# robotic_arm_arduino_uno_shield_ece196.net
KiCad netlist of a schematic drawn in EAGLE
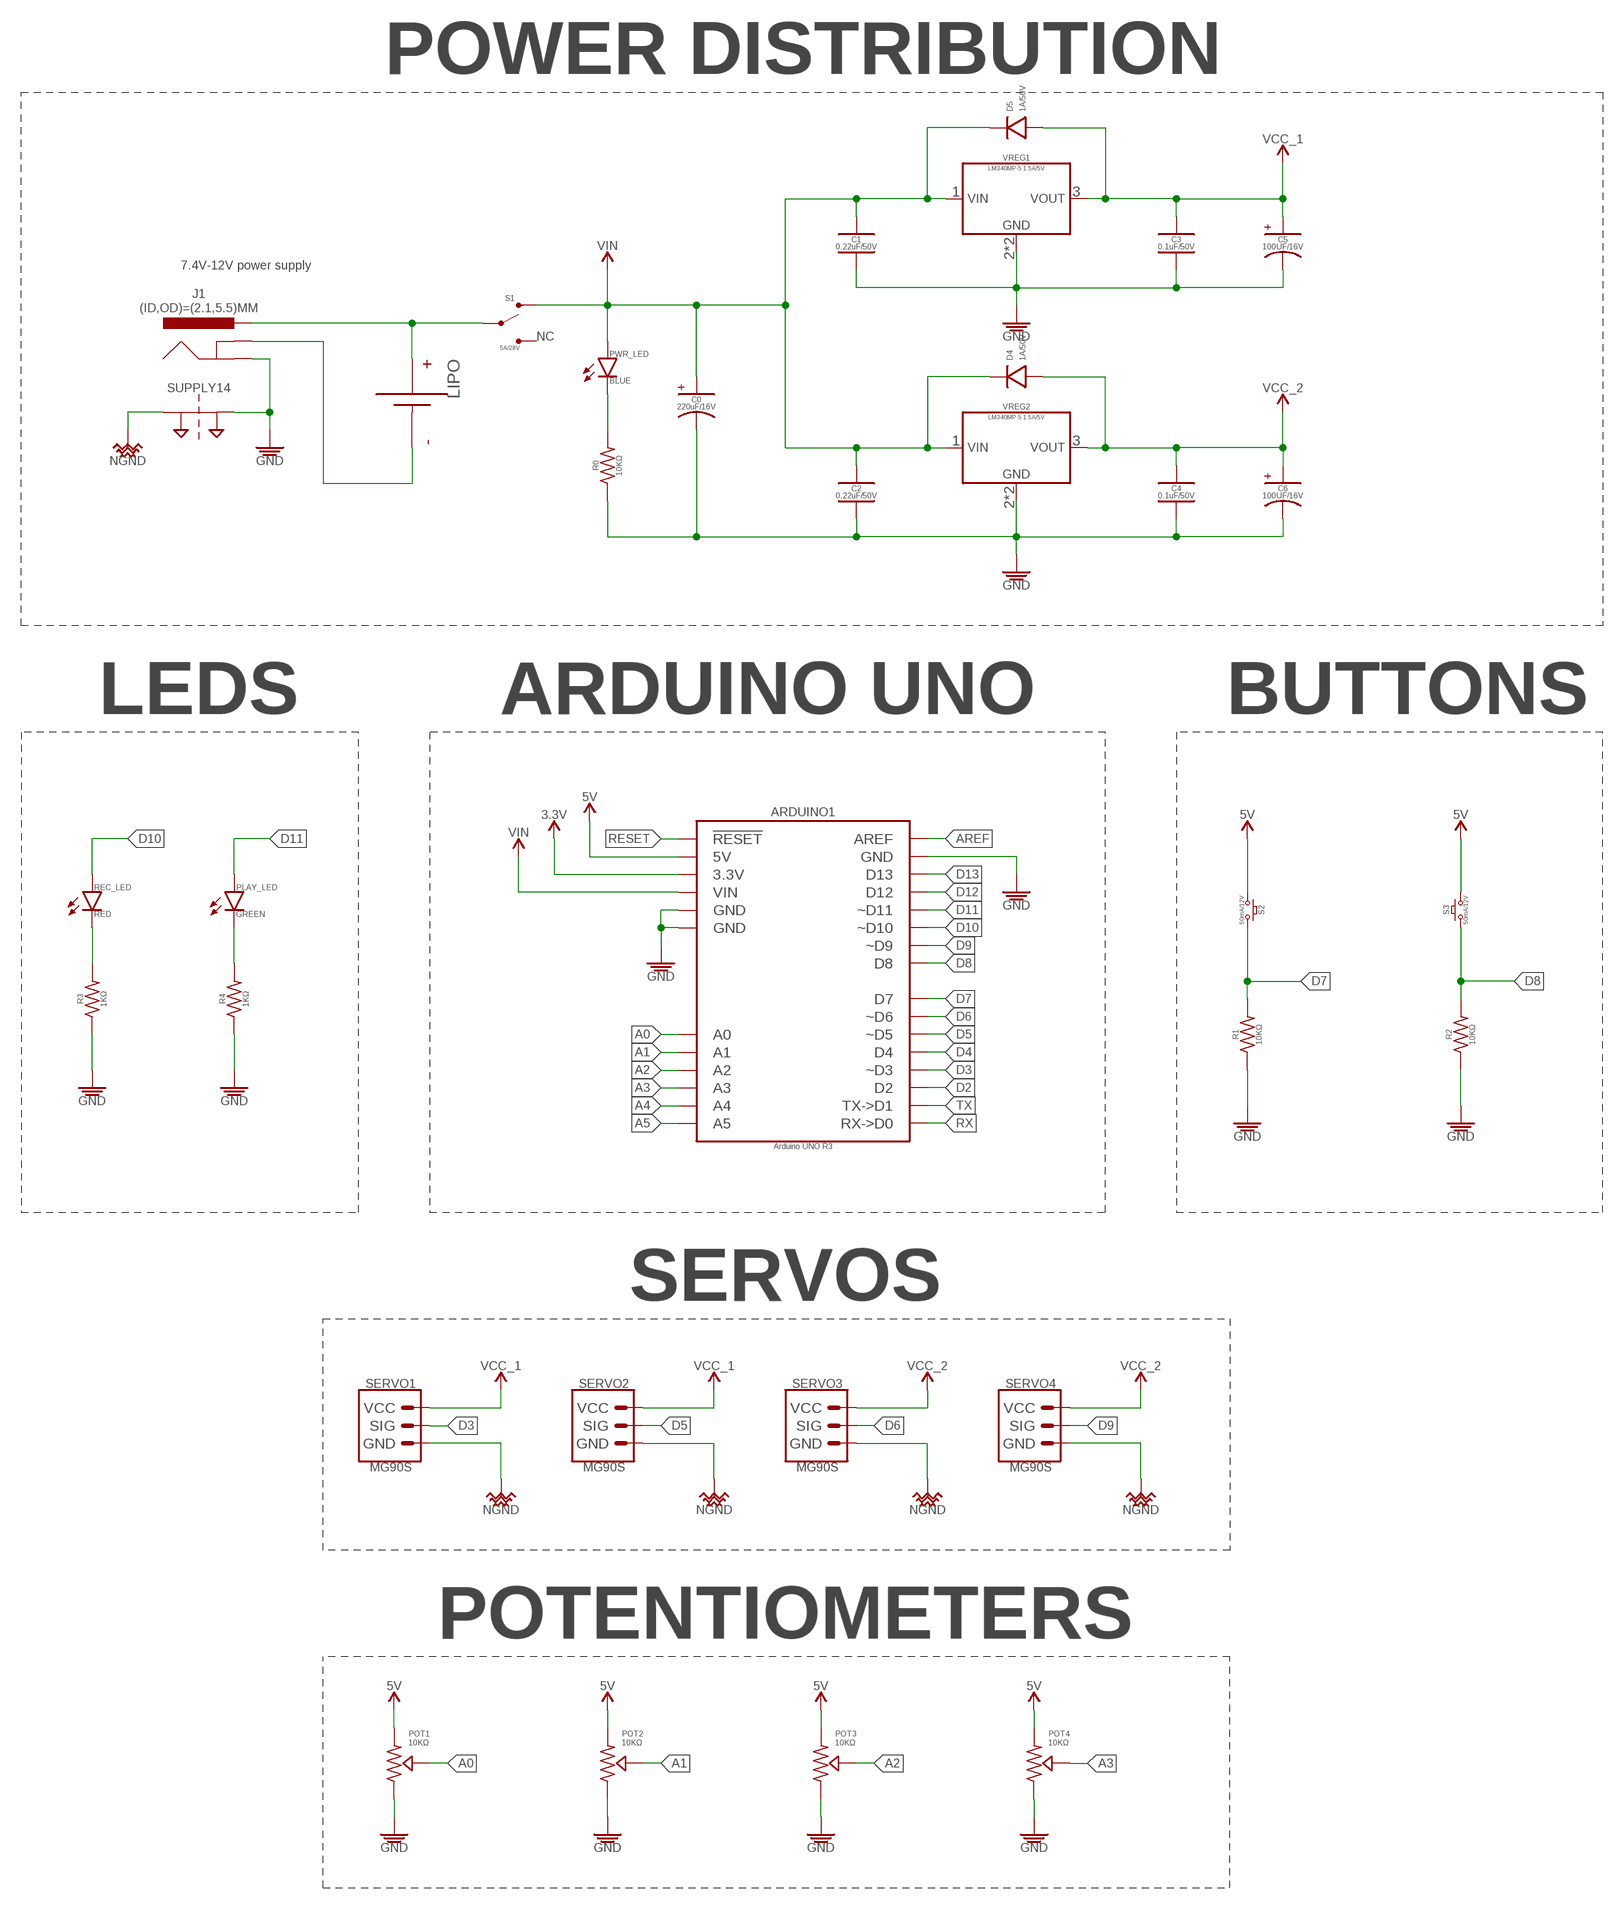
[diagram p0: schematic, sheet 1]

(export (version "E")
  (design (tool "Eeschema 10.0.6"))
  (components
    (comp (ref "ARDUINO1")
      (value "Arduino UNO R3")
      (footprint "eagle-import:ARDUINO_UNO_R3_NO-HOLES_NO-AVR-ISP_NO-I2C_NO-NC_NO-IOREF")
      (fields (field (name "MFR") "Arduino") (field (name "MPN") "A000066"))
      (libsource (lib "eagle-import") (part "ARDUINO_UNO_R3_NO-HOLES_NO-AVR-ISP_NO-I2C_NO-NC_NO-IOREF"))
    )
    (comp (ref "C0")
      (value "220uF/16V")
      (footprint "eagle-import:_AE_SMD_L6.6-W6.6")
      (fields
        (field (name "MFR") "Panasonic Electronic Components")
        (field (name "MPN") "EEE-FT1C221AP")
        (field (name "CREATOR") "MrSwirlyEyes")
      )
      (libsource (lib "eagle-import") (part "220UF-POLARIZED_SMD_16V-20%"))
    )
    (comp (ref "C1")
      (value "0.22uF/50V")
      (footprint "eagle-import:_CER_SMD-805")
      (fields
        (field (name "MFR") "Murata Electronics North America")
        (field (name "MPN") "GRM21BR71H224KA01L")
        (field (name "CREATOR") "MrSwirlyEyes")
      )
      (libsource (lib "eagle-import") (part "0.22UF_SMD-805_50V-10%"))
    )
    (comp (ref "C2")
      (value "0.22uF/50V")
      (footprint "eagle-import:_CER_SMD-805")
      (fields
        (field (name "MFR") "Murata Electronics North America")
        (field (name "MPN") "GRM21BR71H224KA01L")
        (field (name "CREATOR") "MrSwirlyEyes")
      )
      (libsource (lib "eagle-import") (part "0.22UF_SMD-805_50V-10%"))
    )
    (comp (ref "C3")
      (value "0.1uF/50V")
      (footprint "eagle-import:_CER_SMD-805")
      (fields
        (field (name "MFR") "Murata Electronics North America")
        (field (name "MPN") "GRM21BR71H104KA01L")
        (field (name "CREATOR") "MrSwirlyEyes")
      )
      (libsource (lib "eagle-import") (part "0.1UF_SMD-805_50V-10%"))
    )
    (comp (ref "C4")
      (value "0.1uF/50V")
      (footprint "eagle-import:_CER_SMD-805")
      (fields
        (field (name "MFR") "Murata Electronics North America")
        (field (name "MPN") "GRM21BR71H104KA01L")
        (field (name "CREATOR") "MrSwirlyEyes")
      )
      (libsource (lib "eagle-import") (part "0.1UF_SMD-805_50V-10%"))
    )
    (comp (ref "C5")
      (value "100UF/16V")
      (footprint "eagle-import:_AE_SMD_L6.6-W6.6")
      (fields
        (field (name "MFR") "Panasonic Electronic Components")
        (field (name "MPN") "EEE-FK1C101P")
        (field (name "CREATOR") "MrSwirlyEyes")
      )
      (libsource (lib "eagle-import") (part "100UF-POLARIZED_SMD_16V-20%"))
    )
    (comp (ref "C6")
      (value "100UF/16V")
      (footprint "eagle-import:_AE_SMD_L6.6-W6.6")
      (fields
        (field (name "MFR") "Panasonic Electronic Components")
        (field (name "MPN") "EEE-FK1C101P")
        (field (name "CREATOR") "MrSwirlyEyes")
      )
      (libsource (lib "eagle-import") (part "100UF-POLARIZED_SMD_16V-20%"))
    )
    (comp (ref "D4")
      (value "1A/50V")
      (footprint "eagle-import:SOD123F")
      (fields
        (field (name "MFR") "Comchip Technology")
        (field (name "MPN") "CGRKM4001-HF")
        (field (name "CREATOR") "MrSwirlyEyes")
      )
      (libsource (lib "eagle-import") (part "DIODE_GENERAL-PURPOSE_SMD_GP_1A-50V"))
    )
    (comp (ref "D5")
      (value "1A/50V")
      (footprint "eagle-import:SOD123F")
      (fields
        (field (name "MFR") "Comchip Technology")
        (field (name "MPN") "CGRKM4001-HF")
        (field (name "CREATOR") "MrSwirlyEyes")
      )
      (libsource (lib "eagle-import") (part "DIODE_GENERAL-PURPOSE_SMD_GP_1A-50V"))
    )
    (comp (ref "J1")
      (value "(ID,OD)=(2.1,5.5)MM")
      (footprint "eagle-import:POWER_JACK_PTH_ID2.1MM-OD5.5MM")
      (fields (field (name "MFR") "CUI Inc.") (field (name "MPN") "PJ-059A"))
      (libsource (lib "eagle-import") (part "POWER_JACK-BARREL_ID2.1MM-OD5.5MMPTH"))
    )
    (comp (ref "LIPO")
      (value "7.4V")
      (footprint "eagle-import:DUAL_PTH_PADS")
      (libsource (lib "eagle-import") (part "BATTERY_LIPO_BATTERY"))
    )
    (comp (ref "PLAY_LED")
      (value "GREEN")
      (footprint "eagle-import:LED_SMD-805_")
      (fields
        (field (name "MFR") "Lite-On Inc.")
        (field (name "MPN") "LTST-C170KGKT")
        (field (name "CREATOR") "MrSwirlyEyes")
      )
      (libsource (lib "eagle-import") (part "LED_SMD-0805_DISCRETE_GREEN"))
    )
    (comp (ref "POT1")
      (value "10KΩ")
      (footprint "eagle-import:CONNECTOR_POTENTIOMETER_NO-MARKINGS_FEMALE-HEADER")
      (fields
        (field (name "MFR") "TT Electronics/BI")
        (field (name "MPN") "P160KN2-0QA25B10K")
        (field (name "CREATOR") "MrSwirlyEyes")
      )
      (libsource (lib "eagle-import") (part "POTENTIOMETER_NO-MARKINGS_VERT-FEMALE"))
    )
    (comp (ref "POT2")
      (value "10KΩ")
      (footprint "eagle-import:CONNECTOR_POTENTIOMETER_NO-MARKINGS_FEMALE-HEADER")
      (fields
        (field (name "MFR") "TT Electronics/BI")
        (field (name "MPN") "P160KN2-0QA25B10K")
        (field (name "CREATOR") "MrSwirlyEyes")
      )
      (libsource (lib "eagle-import") (part "POTENTIOMETER_NO-MARKINGS_VERT-FEMALE"))
    )
    (comp (ref "POT3")
      (value "10KΩ")
      (footprint "eagle-import:CONNECTOR_POTENTIOMETER_NO-MARKINGS_FEMALE-HEADER")
      (fields
        (field (name "MFR") "TT Electronics/BI")
        (field (name "MPN") "P160KN2-0QA25B10K")
        (field (name "CREATOR") "MrSwirlyEyes")
      )
      (libsource (lib "eagle-import") (part "POTENTIOMETER_NO-MARKINGS_VERT-FEMALE"))
    )
    (comp (ref "POT4")
      (value "10KΩ")
      (footprint "eagle-import:CONNECTOR_POTENTIOMETER_NO-MARKINGS_FEMALE-HEADER")
      (fields
        (field (name "MFR") "TT Electronics/BI")
        (field (name "MPN") "P160KN2-0QA25B10K")
        (field (name "CREATOR") "MrSwirlyEyes")
      )
      (libsource (lib "eagle-import") (part "POTENTIOMETER_NO-MARKINGS_VERT-FEMALE"))
    )
    (comp (ref "PWR_LED")
      (value "BLUE")
      (footprint "eagle-import:LED_SMD-805_")
      (fields
        (field (name "MFR") "Lite-On Inc.")
        (field (name "MPN") "LTST-C170TBKT")
        (field (name "CREATOR") "MrSwirlyEyes")
      )
      (libsource (lib "eagle-import") (part "LED_SMD-0805_DISCRETE_BLUE"))
    )
    (comp (ref "R0")
      (value "10KΩ")
      (footprint "eagle-import:RESISTOR_SMD-805")
      (fields
        (field (name "MFR") "Yageo")
        (field (name "MPN") "RC0805JR-0710KL")
        (field (name "CREATOR") "Kenmei")
      )
      (libsource (lib "eagle-import") (part "10KΩ_SMD-0805_1/8W-5%"))
    )
    (comp (ref "R1")
      (value "10KΩ")
      (footprint "eagle-import:RESISTOR_SMD-805")
      (fields
        (field (name "MFR") "Yageo")
        (field (name "MPN") "RC0805JR-0710KL")
        (field (name "CREATOR") "Kenmei")
      )
      (libsource (lib "eagle-import") (part "10KΩ_SMD-0805_1/8W-5%"))
    )
    (comp (ref "R2")
      (value "10KΩ")
      (footprint "eagle-import:RESISTOR_SMD-805")
      (fields
        (field (name "MFR") "Yageo")
        (field (name "MPN") "RC0805JR-0710KL")
        (field (name "CREATOR") "Kenmei")
      )
      (libsource (lib "eagle-import") (part "10KΩ_SMD-0805_1/8W-5%"))
    )
    (comp (ref "R3")
      (value "1KΩ")
      (footprint "eagle-import:RESISTOR_SMD-805")
      (fields
        (field (name "MFR") "Yageo")
        (field (name "MPN") "RC0805JR-071KL ")
        (field (name "CREATOR") "Kenmei")
      )
      (libsource (lib "eagle-import") (part "1KΩ_SMD-0805_1/8W-5%"))
    )
    (comp (ref "R4")
      (value "1KΩ")
      (footprint "eagle-import:RESISTOR_SMD-805")
      (fields
        (field (name "MFR") "Yageo")
        (field (name "MPN") "RC0805JR-071KL ")
        (field (name "CREATOR") "Kenmei")
      )
      (libsource (lib "eagle-import") (part "1KΩ_SMD-0805_1/8W-5%"))
    )
    (comp (ref "REC_LED")
      (value "RED")
      (footprint "eagle-import:LED_SMD-805_")
      (fields
        (field (name "MFR") "Lite-On Inc.")
        (field (name "MPN") "LTST-C170KRKT")
        (field (name "CREATOR") "MrSwirlyEyes")
      )
      (libsource (lib "eagle-import") (part "LED_SMD-0805_DISCRETE_RED"))
    )
    (comp (ref "S1")
      (value "5A/28V")
      (footprint "eagle-import:SW_TOGGLE_SPDT_5A-28V_13L-7W")
      (fields
        (field (name "MFR") "E-Switch")
        (field (name "MPN") "100SP1T1B4M2QE")
        (field (name "CREATOR") "MrSwirlyEyes")
      )
      (libsource (lib "eagle-import") (part "SWITCH_SPDT_VERT_PTH_5A-28V_13L-7W"))
    )
    (comp (ref "S2")
      (value "50mA/12V")
      (footprint "eagle-import:BTN_MOMENTARY_SPST-NO_PTH_L12-W12")
      (fields
        (field (name "MFR") "SparkFun Electronics")
        (field (name "MPN") "COM-10302")
        (field (name "CREATOR") "MrSwirlyEyes")
      )
      (libsource (lib "eagle-import") (part "SWITCH_MOMENTARYSPST-PTH-L12-W12-H7.2"))
    )
    (comp (ref "S3")
      (value "50mA/12V")
      (footprint "eagle-import:BTN_MOMENTARY_SPST-NO_PTH_L12-W12")
      (fields
        (field (name "MFR") "SparkFun Electronics")
        (field (name "MPN") "COM-10302")
        (field (name "CREATOR") "MrSwirlyEyes")
      )
      (libsource (lib "eagle-import") (part "SWITCH_MOMENTARYSPST-PTH-L12-W12-H7.2"))
    )
    (comp (ref "SERVO1")
      (value "MG90S")
      (footprint "eagle-import:CONNECTOR_SERVO")
      (fields (field (name "MFR") "TowerPro") (field (name "CREATOR") "MrSwirlyEyes"))
      (libsource (lib "eagle-import") (part "SERVOMG90S"))
    )
    (comp (ref "SERVO2")
      (value "MG90S")
      (footprint "eagle-import:CONNECTOR_SERVO")
      (fields (field (name "MFR") "TowerPro") (field (name "CREATOR") "MrSwirlyEyes"))
      (libsource (lib "eagle-import") (part "SERVOMG90S"))
    )
    (comp (ref "SERVO3")
      (value "MG90S")
      (footprint "eagle-import:CONNECTOR_SERVO")
      (fields (field (name "MFR") "TowerPro") (field (name "CREATOR") "MrSwirlyEyes"))
      (libsource (lib "eagle-import") (part "SERVOMG90S"))
    )
    (comp (ref "SERVO4")
      (value "MG90S")
      (footprint "eagle-import:CONNECTOR_SERVO")
      (fields (field (name "MFR") "TowerPro") (field (name "CREATOR") "MrSwirlyEyes"))
      (libsource (lib "eagle-import") (part "SERVOMG90S"))
    )
    (comp (ref "SUPPLY14")
      (value "2PT_GND_TIE")
      (footprint "eagle-import:2PT_GND_TIE")
      (libsource (lib "eagle-import") (part "2PT_GND_TIE"))
    )
    (comp (ref "VREG1")
      (value "LM340MP-5 1.5A/5V")
      (footprint "eagle-import:SOT223-4")
      (fields
        (field (name "MFR") "Texas Instruments")
        (field (name "MPN") "LM340MP-5.0/NOPB")
        (field (name "CREATOR") "MrSwirlyEyes")
      )
      (libsource (lib "eagle-import") (part "VREG_LINEAR_FIXED_LM340MP-5_1.5A-5V"))
    )
    (comp (ref "VREG2")
      (value "LM340MP-5 1.5A/5V")
      (footprint "eagle-import:SOT223-4")
      (fields
        (field (name "MFR") "Texas Instruments")
        (field (name "MPN") "LM340MP-5.0/NOPB")
        (field (name "CREATOR") "MrSwirlyEyes")
      )
      (libsource (lib "eagle-import") (part "VREG_LINEAR_FIXED_LM340MP-5_1.5A-5V"))
    )
  )
  (nets
    (net (code "1") (name "3.3V") (class "Default")
      (node (ref "ARDUINO1") (pin "3.3V") (pinfunction "3.3V_3.3V") (pintype "bidirectional"))
    )
    (net (code "2") (name "5V") (class "Default")
      (node (ref "ARDUINO1") (pin "5V") (pinfunction "5V_5V") (pintype "bidirectional"))
      (node (ref "POT1") (pin "CCW") (pinfunction "CCW_CCW") (pintype "passive"))
      (node (ref "POT2") (pin "CCW") (pinfunction "CCW_CCW") (pintype "passive"))
      (node (ref "POT3") (pin "CCW") (pinfunction "CCW_CCW") (pintype "passive"))
      (node (ref "POT4") (pin "CCW") (pinfunction "CCW_CCW") (pintype "passive"))
      (node (ref "S2") (pin "1") (pinfunction "1_1") (pintype "passive"))
      (node (ref "S3") (pin "3") (pinfunction "2_3") (pintype "passive"))
    )
    (net (code "3") (name "A0") (class "Default")
      (node (ref "ARDUINO1") (pin "A0") (pinfunction "A0_A0") (pintype "bidirectional"))
      (node (ref "POT1") (pin "S") (pinfunction "S_S") (pintype "passive"))
    )
    (net (code "4") (name "A1") (class "Default")
      (node (ref "ARDUINO1") (pin "A1") (pinfunction "A1_A1") (pintype "bidirectional"))
      (node (ref "POT2") (pin "S") (pinfunction "S_S") (pintype "passive"))
    )
    (net (code "5") (name "A2") (class "Default")
      (node (ref "ARDUINO1") (pin "A2") (pinfunction "A2_A2") (pintype "bidirectional"))
      (node (ref "POT3") (pin "S") (pinfunction "S_S") (pintype "passive"))
    )
    (net (code "6") (name "A3") (class "Default")
      (node (ref "ARDUINO1") (pin "A3") (pinfunction "A3_A3") (pintype "bidirectional"))
      (node (ref "POT4") (pin "S") (pinfunction "S_S") (pintype "passive"))
    )
    (net (code "7") (name "A4") (class "Default")
      (node (ref "ARDUINO1") (pin "A4") (pinfunction "A4_A4") (pintype "bidirectional"))
    )
    (net (code "8") (name "A5") (class "Default")
      (node (ref "ARDUINO1") (pin "A5") (pinfunction "A5_A5") (pintype "bidirectional"))
    )
    (net (code "9") (name "AREF") (class "Default")
      (node (ref "ARDUINO1") (pin "AREF") (pinfunction "AREF_AREF") (pintype "bidirectional"))
    )
    (net (code "10") (name "D2") (class "Default")
      (node (ref "ARDUINO1") (pin "D2") (pinfunction "D2_D2") (pintype "bidirectional"))
    )
    (net (code "11") (name "D3") (class "Default")
      (node (ref "ARDUINO1") (pin "D3") (pinfunction "~{D3}_D3") (pintype "bidirectional"))
      (node (ref "SERVO1") (pin "1") (pinfunction "SIG_1") (pintype "passive"))
    )
    (net (code "12") (name "D4") (class "Default")
      (node (ref "ARDUINO1") (pin "D4") (pinfunction "D4_D4") (pintype "bidirectional"))
    )
    (net (code "13") (name "D5") (class "Default")
      (node (ref "ARDUINO1") (pin "D5") (pinfunction "~{D5}_D5") (pintype "bidirectional"))
      (node (ref "SERVO2") (pin "1") (pinfunction "SIG_1") (pintype "passive"))
    )
    (net (code "14") (name "D6") (class "Default")
      (node (ref "ARDUINO1") (pin "D6") (pinfunction "~{D6}_D6") (pintype "bidirectional"))
      (node (ref "SERVO3") (pin "1") (pinfunction "SIG_1") (pintype "passive"))
    )
    (net (code "15") (name "D7") (class "Default")
      (node (ref "ARDUINO1") (pin "D7") (pinfunction "D7_D7") (pintype "bidirectional"))
      (node (ref "R1") (pin "2") (pinfunction "2_2") (pintype "passive"))
      (node (ref "S2") (pin "3") (pinfunction "2_3") (pintype "passive"))
    )
    (net (code "16") (name "D8") (class "Default")
      (node (ref "ARDUINO1") (pin "D8") (pinfunction "D8_D8") (pintype "bidirectional"))
      (node (ref "R2") (pin "2") (pinfunction "2_2") (pintype "passive"))
      (node (ref "S3") (pin "1") (pinfunction "1_1") (pintype "passive"))
    )
    (net (code "17") (name "D9") (class "Default")
      (node (ref "ARDUINO1") (pin "D9") (pinfunction "~{D9}_D9") (pintype "bidirectional"))
      (node (ref "SERVO4") (pin "1") (pinfunction "SIG_1") (pintype "passive"))
    )
    (net (code "18") (name "D10") (class "Default")
      (node (ref "ARDUINO1") (pin "D10") (pinfunction "~{D10}_D10") (pintype "bidirectional"))
      (node (ref "REC_LED") (pin "A") (pinfunction "A_A") (pintype "passive"))
    )
    (net (code "19") (name "D11") (class "Default")
      (node (ref "ARDUINO1") (pin "D11") (pinfunction "~{D11}_D11") (pintype "bidirectional"))
      (node (ref "PLAY_LED") (pin "A") (pinfunction "A_A") (pintype "passive"))
    )
    (net (code "20") (name "D12") (class "Default")
      (node (ref "ARDUINO1") (pin "D12") (pinfunction "D12_D12") (pintype "bidirectional"))
    )
    (net (code "21") (name "D13") (class "Default")
      (node (ref "ARDUINO1") (pin "D13") (pinfunction "D13_D13") (pintype "bidirectional"))
    )
    (net (code "22") (name "GND") (class "Default")
      (node (ref "ARDUINO1") (pin "GND@1") (pinfunction "GND_GND@1") (pintype "bidirectional"))
      (node (ref "ARDUINO1") (pin "GND@2") (pinfunction "GND_GND@2") (pintype "bidirectional"))
      (node (ref "ARDUINO1") (pin "GND@3") (pinfunction "GND_GND@3") (pintype "bidirectional"))
      (node (ref "C0") (pin "K") (pinfunction "K_K") (pintype "passive"))
      (node (ref "C1") (pin "2") (pinfunction "2_2") (pintype "passive"))
      (node (ref "C2") (pin "2") (pinfunction "2_2") (pintype "passive"))
      (node (ref "C3") (pin "2") (pinfunction "2_2") (pintype "passive"))
      (node (ref "C4") (pin "2") (pinfunction "2_2") (pintype "passive"))
      (node (ref "C5") (pin "K") (pinfunction "K_K") (pintype "passive"))
      (node (ref "C6") (pin "K") (pinfunction "K_K") (pintype "passive"))
      (node (ref "J1") (pin "GND@1") (pinfunction "GND_GND@1") (pintype "bidirectional"))
      (node (ref "POT1") (pin "CW") (pinfunction "CW_CW") (pintype "passive"))
      (node (ref "POT2") (pin "CW") (pinfunction "CW_CW") (pintype "passive"))
      (node (ref "POT3") (pin "CW") (pinfunction "CW_CW") (pintype "passive"))
      (node (ref "POT4") (pin "CW") (pinfunction "CW_CW") (pintype "passive"))
      (node (ref "R0") (pin "1") (pinfunction "1_1") (pintype "passive"))
      (node (ref "R1") (pin "1") (pinfunction "1_1") (pintype "passive"))
      (node (ref "R2") (pin "1") (pinfunction "1_1") (pintype "passive"))
      (node (ref "R3") (pin "1") (pinfunction "1_1") (pintype "passive"))
      (node (ref "R4") (pin "1") (pinfunction "1_1") (pintype "passive"))
      (node (ref "SUPPLY14") (pin "P$2") (pinfunction "P$2_P$2") (pintype "bidirectional"))
      (node (ref "VREG1") (pin "2") (pinfunction "GND_2") (pintype "bidirectional"))
      (node (ref "VREG1") (pin "TAB") (pinfunction "GND_TAB") (pintype "bidirectional"))
      (node (ref "VREG2") (pin "2") (pinfunction "GND_2") (pintype "bidirectional"))
      (node (ref "VREG2") (pin "TAB") (pinfunction "GND_TAB") (pintype "bidirectional"))
    )
    (net (code "23") (name "NGND") (class "Default")
      (node (ref "SERVO1") (pin "3") (pinfunction "GND_3") (pintype "passive"))
      (node (ref "SERVO2") (pin "3") (pinfunction "GND_3") (pintype "passive"))
      (node (ref "SERVO3") (pin "3") (pinfunction "GND_3") (pintype "passive"))
      (node (ref "SERVO4") (pin "3") (pinfunction "GND_3") (pintype "passive"))
      (node (ref "SUPPLY14") (pin "P$1") (pinfunction "P$1_P$1") (pintype "bidirectional"))
    )
    (net (code "24") (name "Net-(LIPO-N)") (class "Default")
      (node (ref "J1") (pin "GND@2") (pinfunction "GND_GND@2") (pintype "bidirectional"))
      (node (ref "LIPO") (pin "-") (pinfunction "N_-") (pintype "bidirectional"))
    )
    (net (code "25") (name "Net-(LIPO-P)") (class "Default")
      (node (ref "J1") (pin "PWR") (pinfunction "PWR_PWR") (pintype "bidirectional"))
      (node (ref "LIPO") (pin "+") (pinfunction "P_+") (pintype "bidirectional"))
      (node (ref "S1") (pin "2") (pinfunction "2_2") (pintype "passive"))
    )
    (net (code "26") (name "Net-(PLAY_LED-PadK)") (class "Default")
      (node (ref "PLAY_LED") (pin "K") (pinfunction "K_K") (pintype "passive"))
      (node (ref "R4") (pin "2") (pinfunction "2_2") (pintype "passive"))
    )
    (net (code "27") (name "Net-(PWR_LED-PadK)") (class "Default")
      (node (ref "PWR_LED") (pin "K") (pinfunction "K_K") (pintype "passive"))
      (node (ref "R0") (pin "2") (pinfunction "2_2") (pintype "passive"))
    )
    (net (code "28") (name "Net-(R3-Pad2)") (class "Default")
      (node (ref "R3") (pin "2") (pinfunction "2_2") (pintype "passive"))
      (node (ref "REC_LED") (pin "K") (pinfunction "K_K") (pintype "passive"))
    )
    (net (code "29") (name "RESET") (class "Default")
      (node (ref "ARDUINO1") (pin "RESET@1") (pinfunction "~{RESET}_RESET@1") (pintype "bidirectional"))
    )
    (net (code "30") (name "RX") (class "Default")
      (node (ref "ARDUINO1") (pin "D0") (pinfunction "RX->D0_D0") (pintype "bidirectional"))
    )
    (net (code "31") (name "TX") (class "Default")
      (node (ref "ARDUINO1") (pin "D1") (pinfunction "TX->D1_D1") (pintype "bidirectional"))
    )
    (net (code "32") (name "VCC_1") (class "Default")
      (node (ref "C3") (pin "1") (pinfunction "1_1") (pintype "passive"))
      (node (ref "C5") (pin "A") (pinfunction "A_A") (pintype "passive"))
      (node (ref "D5") (pin "A") (pinfunction "A_A") (pintype "passive"))
      (node (ref "SERVO1") (pin "2") (pinfunction "VCC_2") (pintype "passive"))
      (node (ref "SERVO2") (pin "2") (pinfunction "VCC_2") (pintype "passive"))
      (node (ref "VREG1") (pin "3") (pinfunction "VO_3") (pintype "bidirectional"))
    )
    (net (code "33") (name "VCC_2") (class "Default")
      (node (ref "C4") (pin "1") (pinfunction "1_1") (pintype "passive"))
      (node (ref "C6") (pin "A") (pinfunction "A_A") (pintype "passive"))
      (node (ref "D4") (pin "A") (pinfunction "A_A") (pintype "passive"))
      (node (ref "SERVO3") (pin "2") (pinfunction "VCC_2") (pintype "passive"))
      (node (ref "SERVO4") (pin "2") (pinfunction "VCC_2") (pintype "passive"))
      (node (ref "VREG2") (pin "3") (pinfunction "VO_3") (pintype "bidirectional"))
    )
    (net (code "34") (name "VIN") (class "Default")
      (node (ref "ARDUINO1") (pin "VIN") (pinfunction "VIN_VIN") (pintype "bidirectional"))
      (node (ref "C0") (pin "A") (pinfunction "A_A") (pintype "passive"))
      (node (ref "C1") (pin "1") (pinfunction "1_1") (pintype "passive"))
      (node (ref "C2") (pin "1") (pinfunction "1_1") (pintype "passive"))
      (node (ref "D4") (pin "K") (pinfunction "K_K") (pintype "passive"))
      (node (ref "D5") (pin "K") (pinfunction "K_K") (pintype "passive"))
      (node (ref "PWR_LED") (pin "A") (pinfunction "A_A") (pintype "passive"))
      (node (ref "S1") (pin "1") (pinfunction "1_1") (pintype "passive"))
      (node (ref "VREG1") (pin "1") (pinfunction "VI_1") (pintype "bidirectional"))
      (node (ref "VREG2") (pin "1") (pinfunction "VI_1") (pintype "bidirectional"))
    )
    (net (code "35") (name "unconnected-(S1-Pad3)") (class "Default")
      (node (ref "S1") (pin "3") (pinfunction "3_3") (pintype "passive"))
    )
  )
)
